# daughter.net
KiCad netlist of a schematic drawn in EAGLE
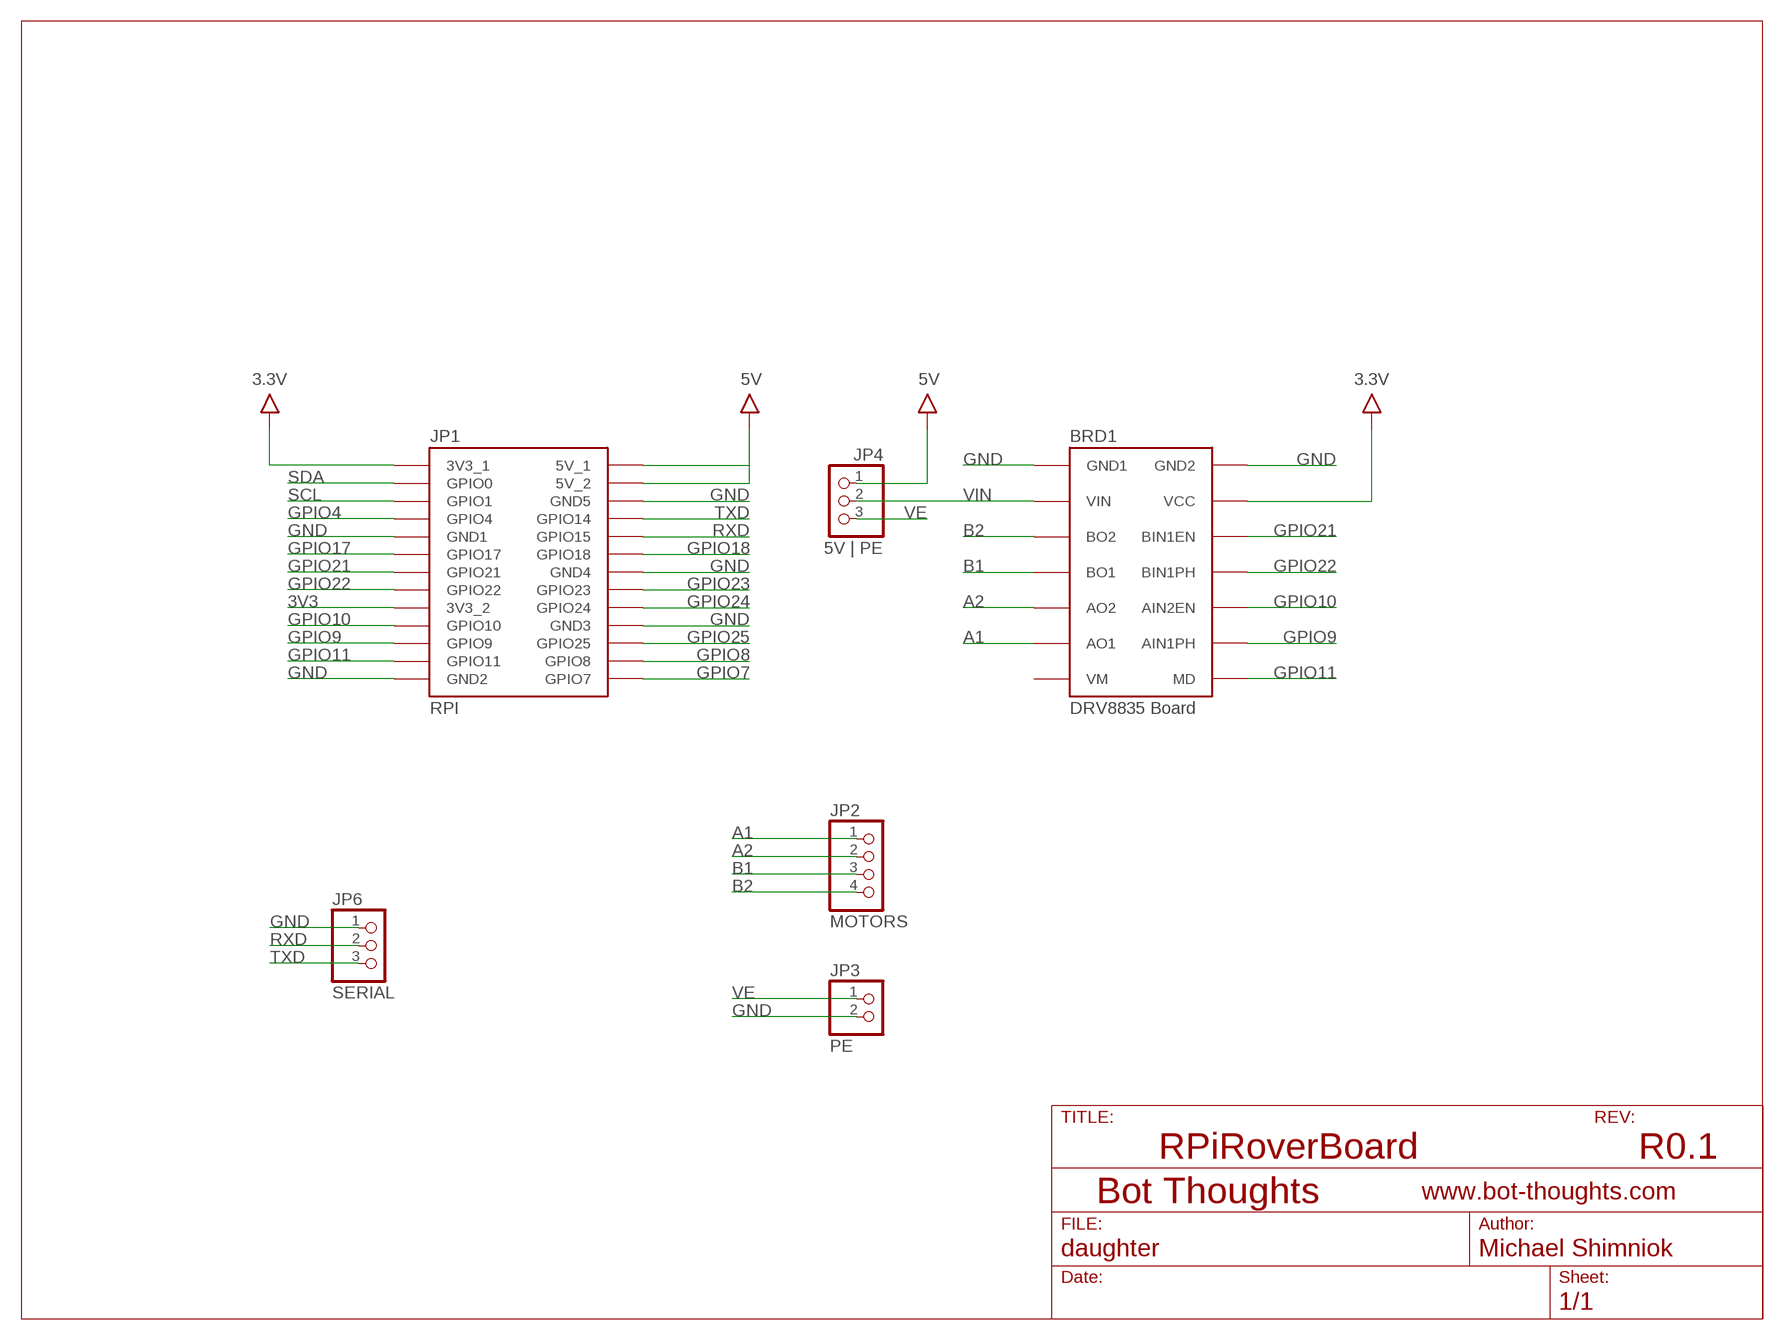
[diagram p0: schematic, sheet 1]

(export (version "E")
  (design (tool "Eeschema 10.0.6"))
  (components
    (comp (ref "BRD1")
      (value "DRV8835 Board")
      (footprint "eagle-import:DRV8835BRD")
      (libsource (lib "eagle-import") (part "DRV8835BRD"))
    )
    (comp (ref "JP1")
      (value "RPI")
      (footprint "eagle-import:RPI")
      (libsource (lib "eagle-import") (part "RPI"))
    )
    (comp (ref "JP2")
      (value "MOTORS")
      (footprint "eagle-import:1X04-S")
      (libsource (lib "eagle-import") (part "PINHD-1X04_2.54-S"))
    )
    (comp (ref "JP3")
      (value "PE")
      (footprint "eagle-import:1X02-S")
      (libsource (lib "eagle-import") (part "PINHD-1X02_2.54-S"))
    )
    (comp (ref "JP4")
      (value "5V | PE")
      (footprint "eagle-import:1X03-S")
      (libsource (lib "eagle-import") (part "PINHD-1X03_2.54-S"))
    )
    (comp (ref "JP6")
      (value "SERIAL")
      (footprint "eagle-import:1X03-S")
      (libsource (lib "eagle-import") (part "PINHD-1X03_2.54-S"))
    )
  )
  (nets
    (net (code "1") (name "/3V3") (class "Default")
      (node (ref "JP1") (pin "3V3_2") (pinfunction "3V3_2_3V3_2") (pintype "bidirectional"))
    )
    (net (code "2") (name "/A1") (class "Default")
      (node (ref "BRD1") (pin "AO1") (pinfunction "AO1_AO1") (pintype "bidirectional"))
      (node (ref "JP2") (pin "1") (pinfunction "1_1") (pintype "passive"))
    )
    (net (code "3") (name "/A2") (class "Default")
      (node (ref "BRD1") (pin "AO2") (pinfunction "AO2_AO2") (pintype "bidirectional"))
      (node (ref "JP2") (pin "2") (pinfunction "2_2") (pintype "passive"))
    )
    (net (code "4") (name "/B1") (class "Default")
      (node (ref "BRD1") (pin "BO1") (pinfunction "BO1_BO1") (pintype "bidirectional"))
      (node (ref "JP2") (pin "3") (pinfunction "3_3") (pintype "passive"))
    )
    (net (code "5") (name "/B2") (class "Default")
      (node (ref "BRD1") (pin "BO2") (pinfunction "BO2_BO2") (pintype "bidirectional"))
      (node (ref "JP2") (pin "4") (pinfunction "4_4") (pintype "passive"))
    )
    (net (code "6") (name "/GND") (class "Default")
      (node (ref "BRD1") (pin "GND1") (pinfunction "GND1_GND1") (pintype "bidirectional"))
      (node (ref "BRD1") (pin "GND2") (pinfunction "GND2_GND2") (pintype "bidirectional"))
      (node (ref "JP1") (pin "GND1") (pinfunction "GND1_GND1") (pintype "bidirectional"))
      (node (ref "JP1") (pin "GND2") (pinfunction "GND2_GND2") (pintype "bidirectional"))
      (node (ref "JP1") (pin "GND3") (pinfunction "GND3_GND3") (pintype "bidirectional"))
      (node (ref "JP1") (pin "GND4") (pinfunction "GND4_GND4") (pintype "bidirectional"))
      (node (ref "JP1") (pin "GND5") (pinfunction "GND5_GND5") (pintype "bidirectional"))
      (node (ref "JP3") (pin "2") (pinfunction "2_2") (pintype "passive"))
      (node (ref "JP6") (pin "1") (pinfunction "1_1") (pintype "passive"))
    )
    (net (code "7") (name "/GPIO4") (class "Default")
      (node (ref "JP1") (pin "GPIO4") (pinfunction "GPIO4_GPIO4") (pintype "bidirectional"))
    )
    (net (code "8") (name "/GPIO7") (class "Default")
      (node (ref "JP1") (pin "GPIO7") (pinfunction "GPIO7_GPIO7") (pintype "bidirectional"))
    )
    (net (code "9") (name "/GPIO8") (class "Default")
      (node (ref "JP1") (pin "GPIO8") (pinfunction "GPIO8_GPIO8") (pintype "bidirectional"))
    )
    (net (code "10") (name "/GPIO9") (class "Default")
      (node (ref "BRD1") (pin "AIN1PH") (pinfunction "AIN1PH_AIN1PH") (pintype "bidirectional"))
      (node (ref "JP1") (pin "GPIO9") (pinfunction "GPIO9_GPIO9") (pintype "bidirectional"))
    )
    (net (code "11") (name "/GPIO10") (class "Default")
      (node (ref "BRD1") (pin "AIN2EN") (pinfunction "AIN2EN_AIN2EN") (pintype "bidirectional"))
      (node (ref "JP1") (pin "GPIO10") (pinfunction "GPIO10_GPIO10") (pintype "bidirectional"))
    )
    (net (code "12") (name "/GPIO11") (class "Default")
      (node (ref "BRD1") (pin "MD") (pinfunction "MD_MD") (pintype "bidirectional"))
      (node (ref "JP1") (pin "GPIO11") (pinfunction "GPIO11_GPIO11") (pintype "bidirectional"))
    )
    (net (code "13") (name "/GPIO17") (class "Default")
      (node (ref "JP1") (pin "GPIO17") (pinfunction "GPIO17_GPIO17") (pintype "bidirectional"))
    )
    (net (code "14") (name "/GPIO18") (class "Default")
      (node (ref "JP1") (pin "GPIO18") (pinfunction "GPIO18_GPIO18") (pintype "bidirectional"))
    )
    (net (code "15") (name "/GPIO21") (class "Default")
      (node (ref "BRD1") (pin "BIN2EN") (pinfunction "BIN1EN_BIN2EN") (pintype "bidirectional"))
      (node (ref "JP1") (pin "GPIO21") (pinfunction "GPIO21_GPIO21") (pintype "bidirectional"))
    )
    (net (code "16") (name "/GPIO22") (class "Default")
      (node (ref "BRD1") (pin "BIN1PH") (pinfunction "BIN1PH_BIN1PH") (pintype "bidirectional"))
      (node (ref "JP1") (pin "GPIO22") (pinfunction "GPIO22_GPIO22") (pintype "bidirectional"))
    )
    (net (code "17") (name "/GPIO23") (class "Default")
      (node (ref "JP1") (pin "GPIO23") (pinfunction "GPIO23_GPIO23") (pintype "bidirectional"))
    )
    (net (code "18") (name "/GPIO24") (class "Default")
      (node (ref "JP1") (pin "GPIO24") (pinfunction "GPIO24_GPIO24") (pintype "bidirectional"))
    )
    (net (code "19") (name "/GPIO25") (class "Default")
      (node (ref "JP1") (pin "GPIO25") (pinfunction "GPIO25_GPIO25") (pintype "bidirectional"))
    )
    (net (code "20") (name "/RXD") (class "Default")
      (node (ref "JP1") (pin "GPIO15") (pinfunction "GPIO15_GPIO15") (pintype "bidirectional"))
      (node (ref "JP6") (pin "2") (pinfunction "2_2") (pintype "passive"))
    )
    (net (code "21") (name "/SCL") (class "Default")
      (node (ref "JP1") (pin "GPIO1") (pinfunction "GPIO1_GPIO1") (pintype "bidirectional"))
    )
    (net (code "22") (name "/SDA") (class "Default")
      (node (ref "JP1") (pin "GPIO0") (pinfunction "GPIO0_GPIO0") (pintype "bidirectional"))
    )
    (net (code "23") (name "/TXD") (class "Default")
      (node (ref "JP1") (pin "GPIO14") (pinfunction "GPIO14_GPIO14") (pintype "bidirectional"))
      (node (ref "JP6") (pin "3") (pinfunction "3_3") (pintype "passive"))
    )
    (net (code "24") (name "/VE") (class "Default")
      (node (ref "JP3") (pin "1") (pinfunction "1_1") (pintype "passive"))
      (node (ref "JP4") (pin "3") (pinfunction "3_3") (pintype "passive"))
    )
    (net (code "25") (name "/VIN") (class "Default")
      (node (ref "BRD1") (pin "VIN") (pinfunction "VIN_VIN") (pintype "bidirectional"))
      (node (ref "JP4") (pin "2") (pinfunction "2_2") (pintype "passive"))
    )
    (net (code "26") (name "3.3V") (class "Default")
      (node (ref "BRD1") (pin "VCC") (pinfunction "VCC_VCC") (pintype "bidirectional"))
      (node (ref "JP1") (pin "3V3_1") (pinfunction "3V3_1_3V3_1") (pintype "bidirectional"))
    )
    (net (code "27") (name "5V") (class "Default")
      (node (ref "JP1") (pin "5V_1") (pinfunction "5V_1_5V_1") (pintype "bidirectional"))
      (node (ref "JP1") (pin "5V_2") (pinfunction "5V_2_5V_2") (pintype "bidirectional"))
      (node (ref "JP4") (pin "1") (pinfunction "1_1") (pintype "passive"))
    )
    (net (code "28") (name "unconnected-(BRD1-PadVM)") (class "Default")
      (node (ref "BRD1") (pin "VM") (pinfunction "VM_VM") (pintype "bidirectional"))
    )
  )
)
